# CAN_transciver.net
KiCad netlist of a schematic drawn in Altium Designer
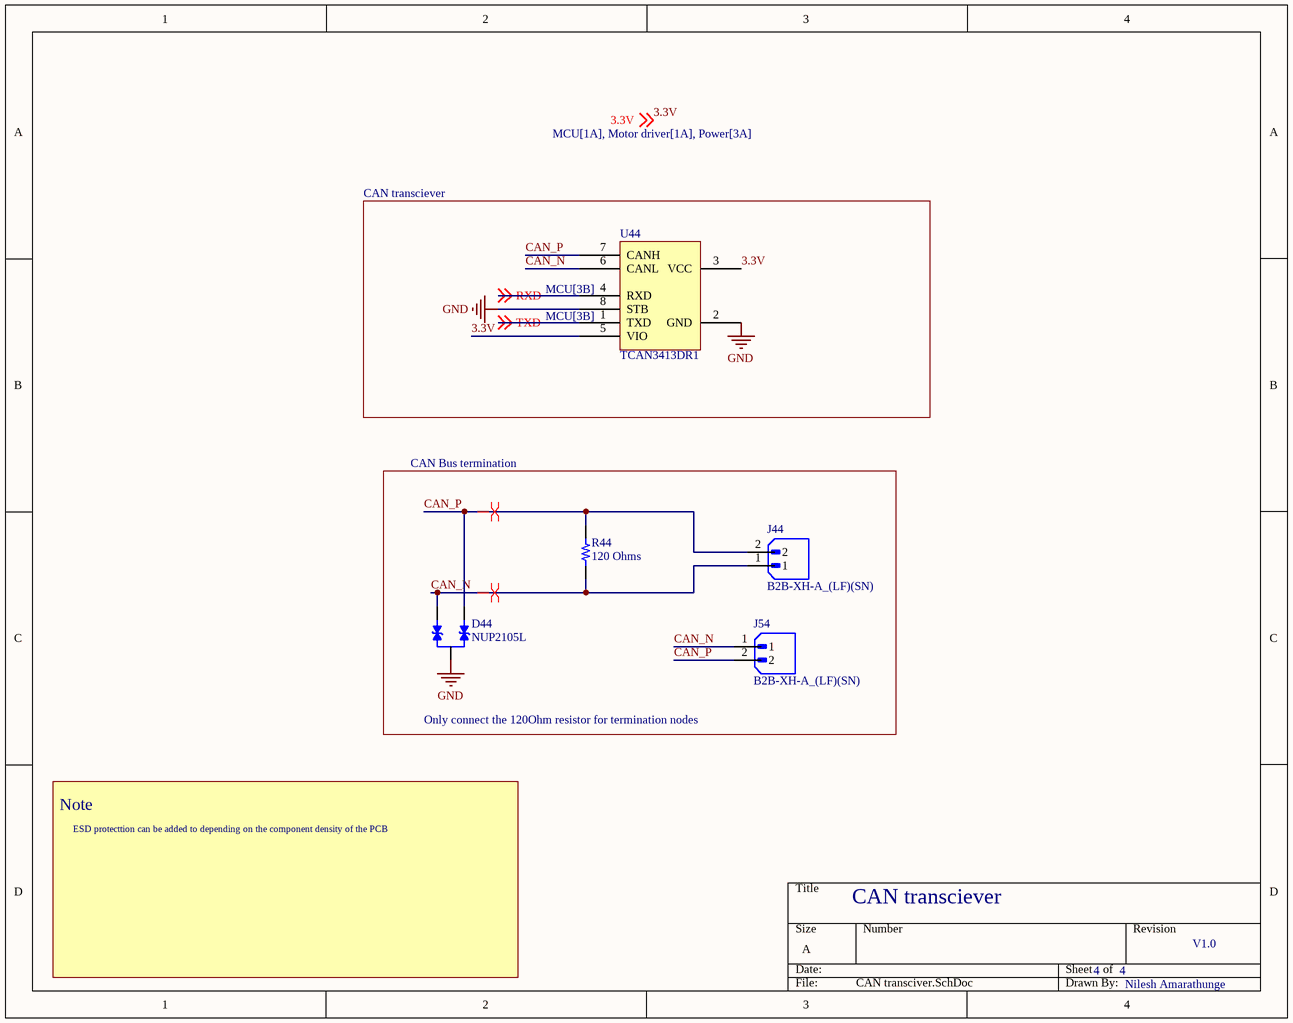
[diagram p0: CAN transciver.SchDoc]

(export (version "E")
  (design (tool "Eeschema 10.0.6"))
  (components
    (comp (ref "D44")
      (value "NUP2105L")
      (footprint "SOT95P240X120-3N")
      (description "ESD, SOT-23, 0.1ÂµA, 24V, Unidir")
      (fields (field (name "MF") "Diotec Semiconductor") (field (name "LCSC PART #") "C14486"))
      (libsource (lib "NUP2105L") (part "NUP2105L"))
    )
    (comp (ref "J44")
      (value "B2B-XH-A_(LF)(SN)")
      (footprint "JST_B2B-XH-A_(LF)(SN)")
      (description "Connector Header Through Hole 2 position 0.098 (2.50mm)")
      (fields (field (name "MF") "JST Sales") (field (name "MP") "B2B-XH-A (LF)(SN)"))
      (libsource (lib "B2B-XH-A_(LF)(SN)") (part "B2B-XH-A_(LF)(SN)"))
    )
    (comp (ref "J54")
      (value "B2B-XH-A_(LF)(SN)")
      (footprint "JST_B2B-XH-A_(LF)(SN)")
      (description "Connector Header Through Hole 2 position 0.098 (2.50mm)")
      (fields (field (name "MF") "JST Sales") (field (name "MP") "B2B-XH-A (LF)(SN)"))
      (libsource (lib "") (part "B2B-XH-A_(LF)(SN)_1"))
    )
    (comp (ref "R44")
      (value "120 Ohms")
      (footprint "RES 0805_2012")
      (description "RES SMD 120 OHM 5% 1/8W 0805")
      (fields
        (field (name "PART NUMBER") "ERJ-6GEYJ121V")
        (field (name "MANUFACTURER") "Panasonic Electronic Components")
      )
      (libsource (lib "Celestial Altium Library - altium_library") (part "Resistor"))
    )
    (comp (ref "U44")
      (value "TCAN3413DR1")
      (footprint "TCAN3413DR1")
      (fields (field (name "LCSC PART #") "C22396693"))
      (libsource (lib "TCAN3413DR1") (part "TCAN3413DR1"))
    )
  )
  (nets
    (net (code "1") (name "/CAN_N") (class "Default")
      (node (ref "D44") (pin "2") (pinfunction "2_2") (pintype "passive"))
      (node (ref "J44") (pin "1") (pinfunction "1_1") (pintype "passive"))
      (node (ref "J54") (pin "1") (pinfunction "1_1") (pintype "passive"))
      (node (ref "R44") (pin "1") (pinfunction "1_1") (pintype "passive"))
      (node (ref "U44") (pin "6") (pinfunction "CANL_6") (pintype "passive"))
    )
    (net (code "2") (name "/CAN_P") (class "Default")
      (node (ref "D44") (pin "1") (pinfunction "1_1") (pintype "passive"))
      (node (ref "J44") (pin "2") (pinfunction "2_2") (pintype "passive"))
      (node (ref "J54") (pin "2") (pinfunction "2_2") (pintype "passive"))
      (node (ref "R44") (pin "2") (pinfunction "2_2") (pintype "passive"))
      (node (ref "U44") (pin "7") (pinfunction "CANH_7") (pintype "passive"))
    )
    (net (code "3") (name "3.3V") (class "Default")
      (node (ref "U44") (pin "3") (pinfunction "VCC_3") (pintype "passive"))
      (node (ref "U44") (pin "5") (pinfunction "VIO_5") (pintype "passive"))
    )
    (net (code "4") (name "GND") (class "Default")
      (node (ref "D44") (pin "3") (pinfunction "3_3") (pintype "passive"))
      (node (ref "U44") (pin "2") (pinfunction "GND_2") (pintype "passive"))
      (node (ref "U44") (pin "8") (pinfunction "STB_8") (pintype "passive"))
    )
    (net (code "5") (name "RXD") (class "Default")
      (node (ref "U44") (pin "4") (pinfunction "RXD_4") (pintype "passive"))
    )
    (net (code "6") (name "TXD") (class "Default")
      (node (ref "U44") (pin "1") (pinfunction "TXD_1") (pintype "passive"))
    )
  )
)
